# MBO.net
KiCad netlist of a schematic drawn in EAGLE
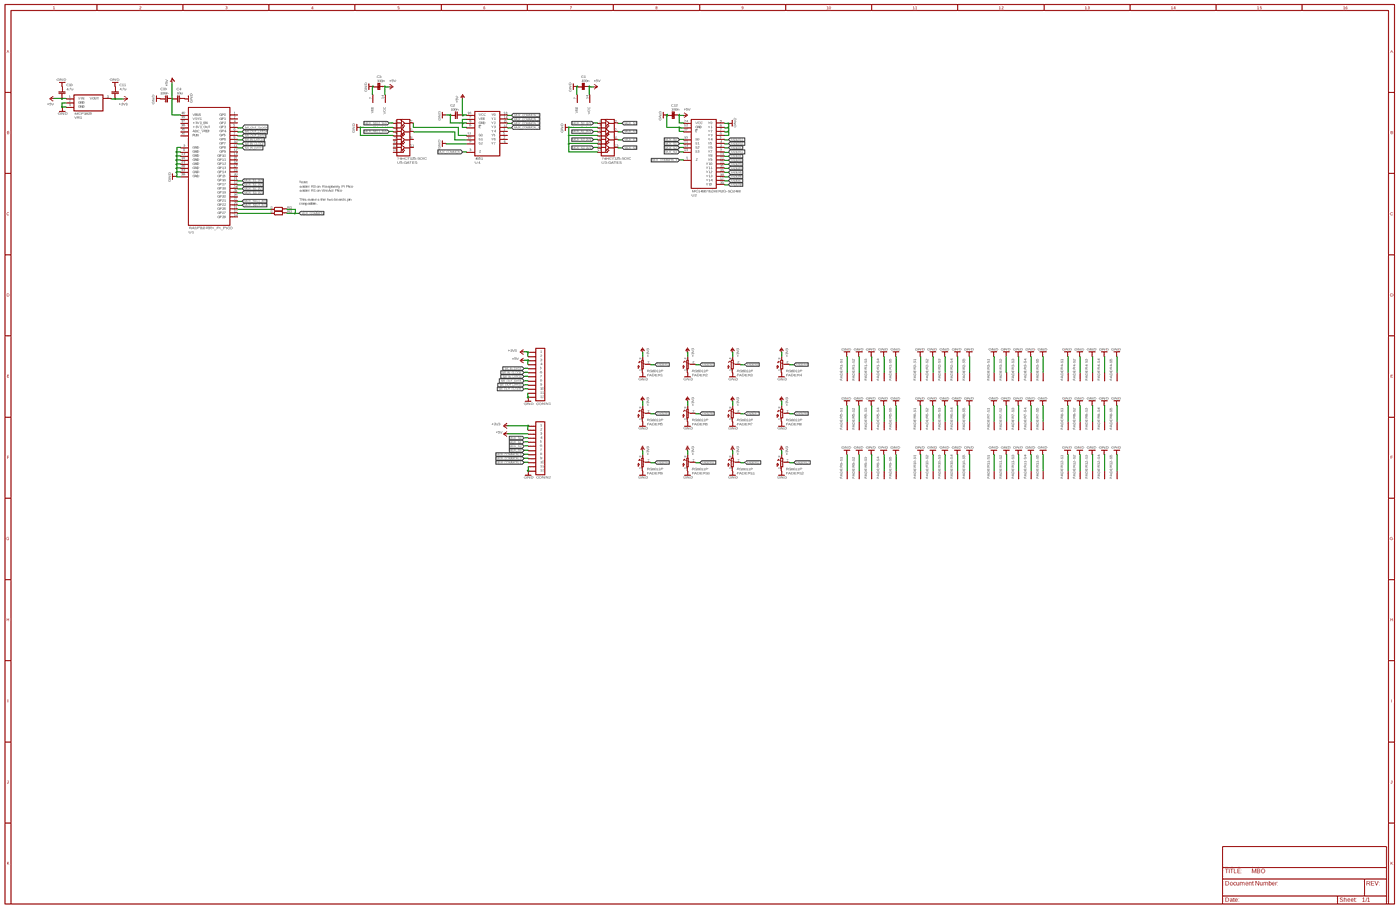
[diagram p0: schematic, sheet 1, overview]
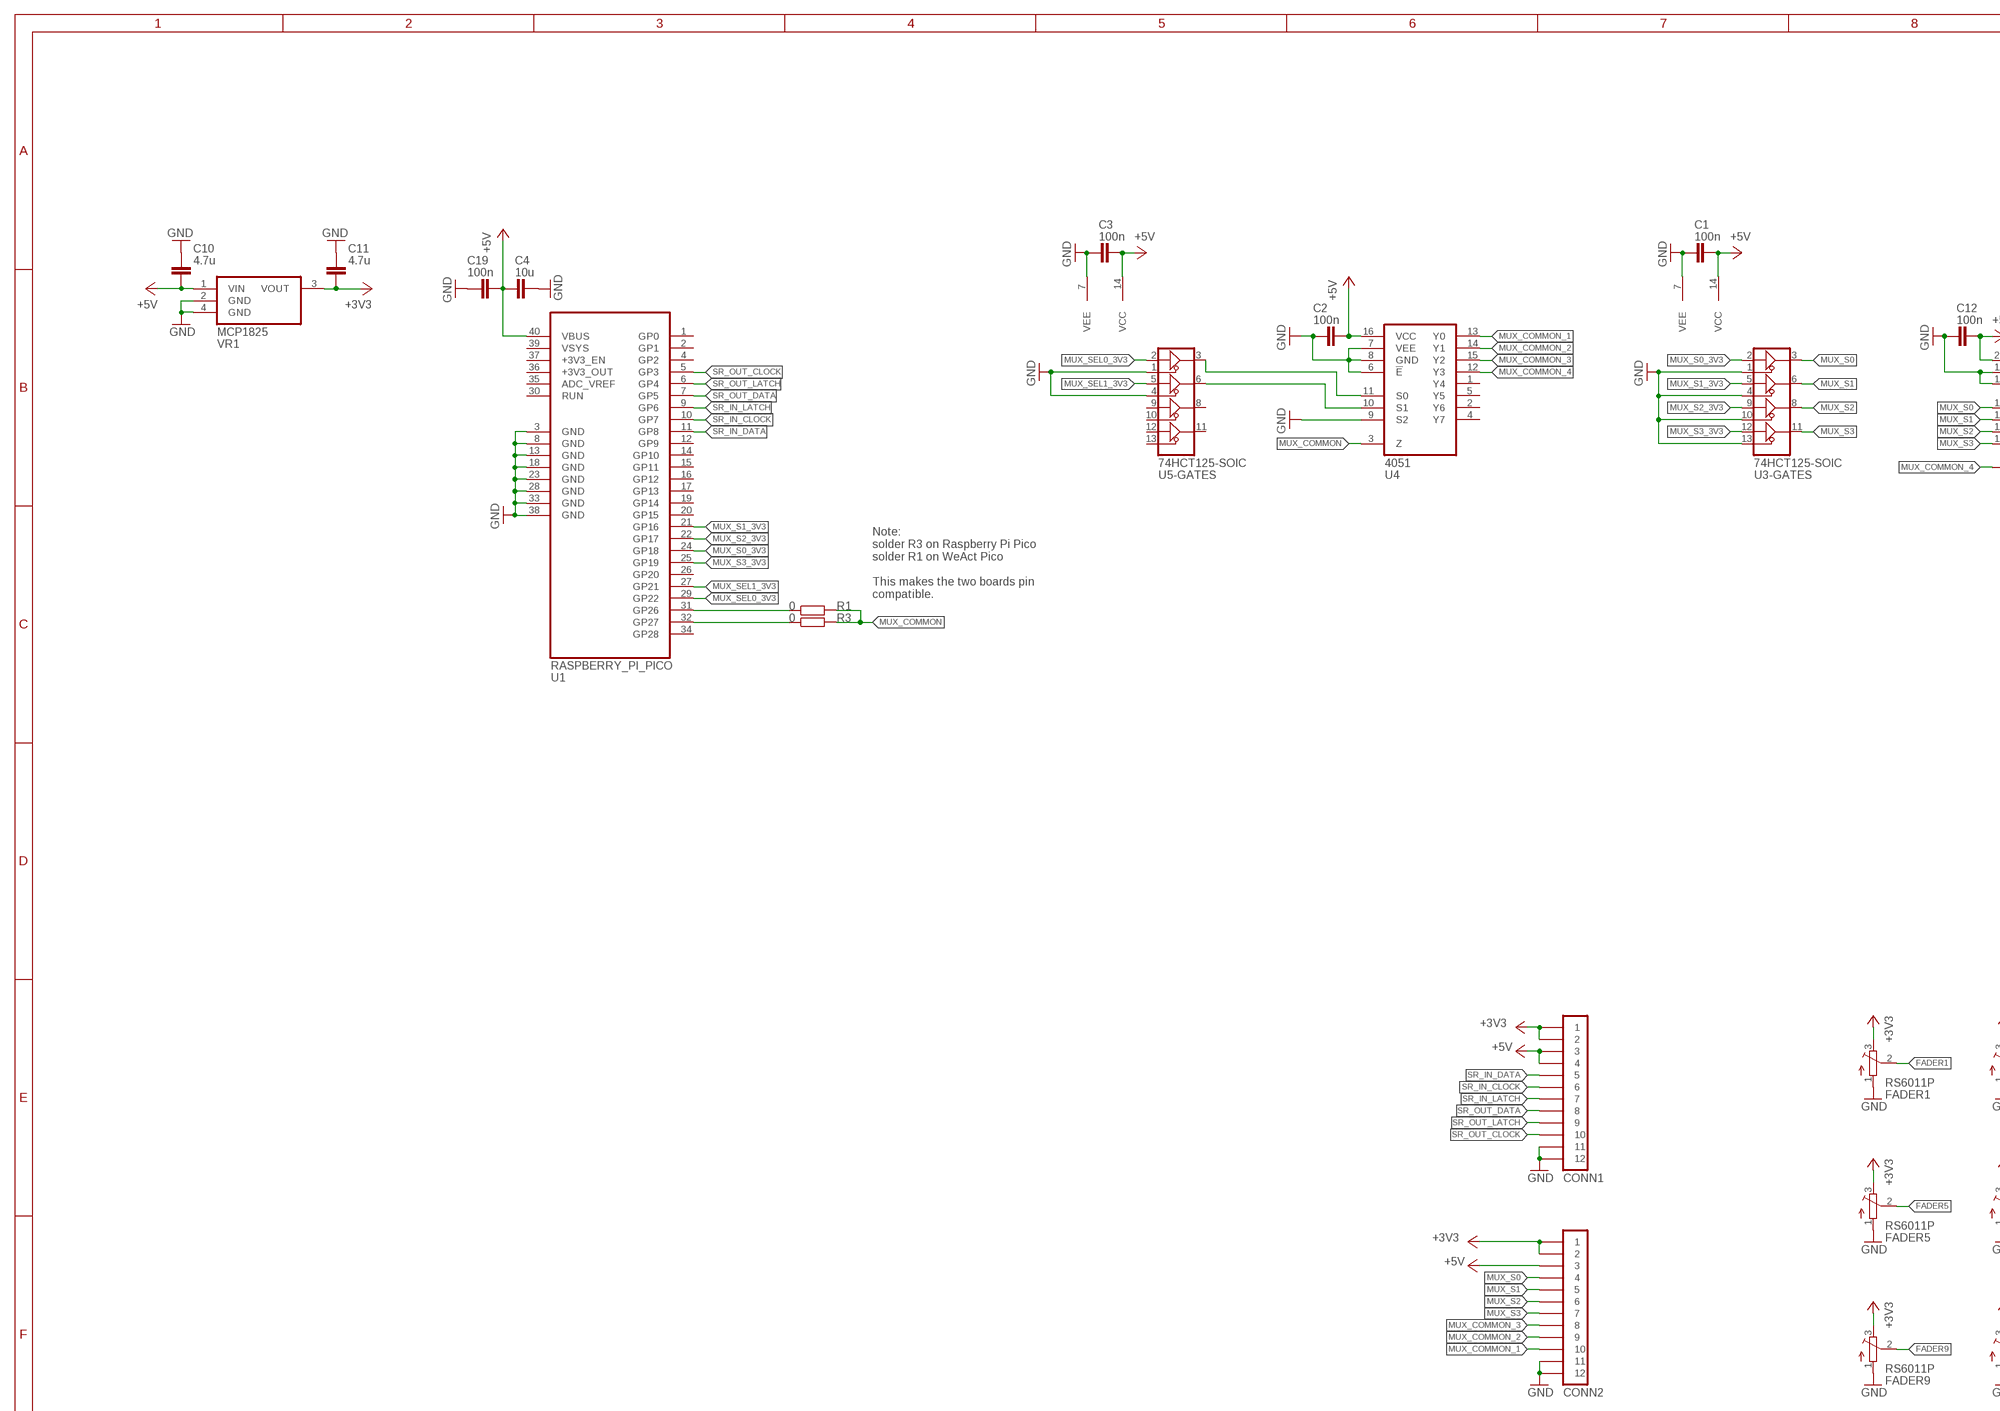
[diagram p1: schematic, sheet 1, part 1 of 4]
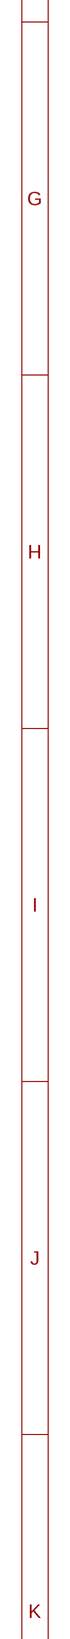
[diagram p2: schematic, sheet 1, part 2 of 4]
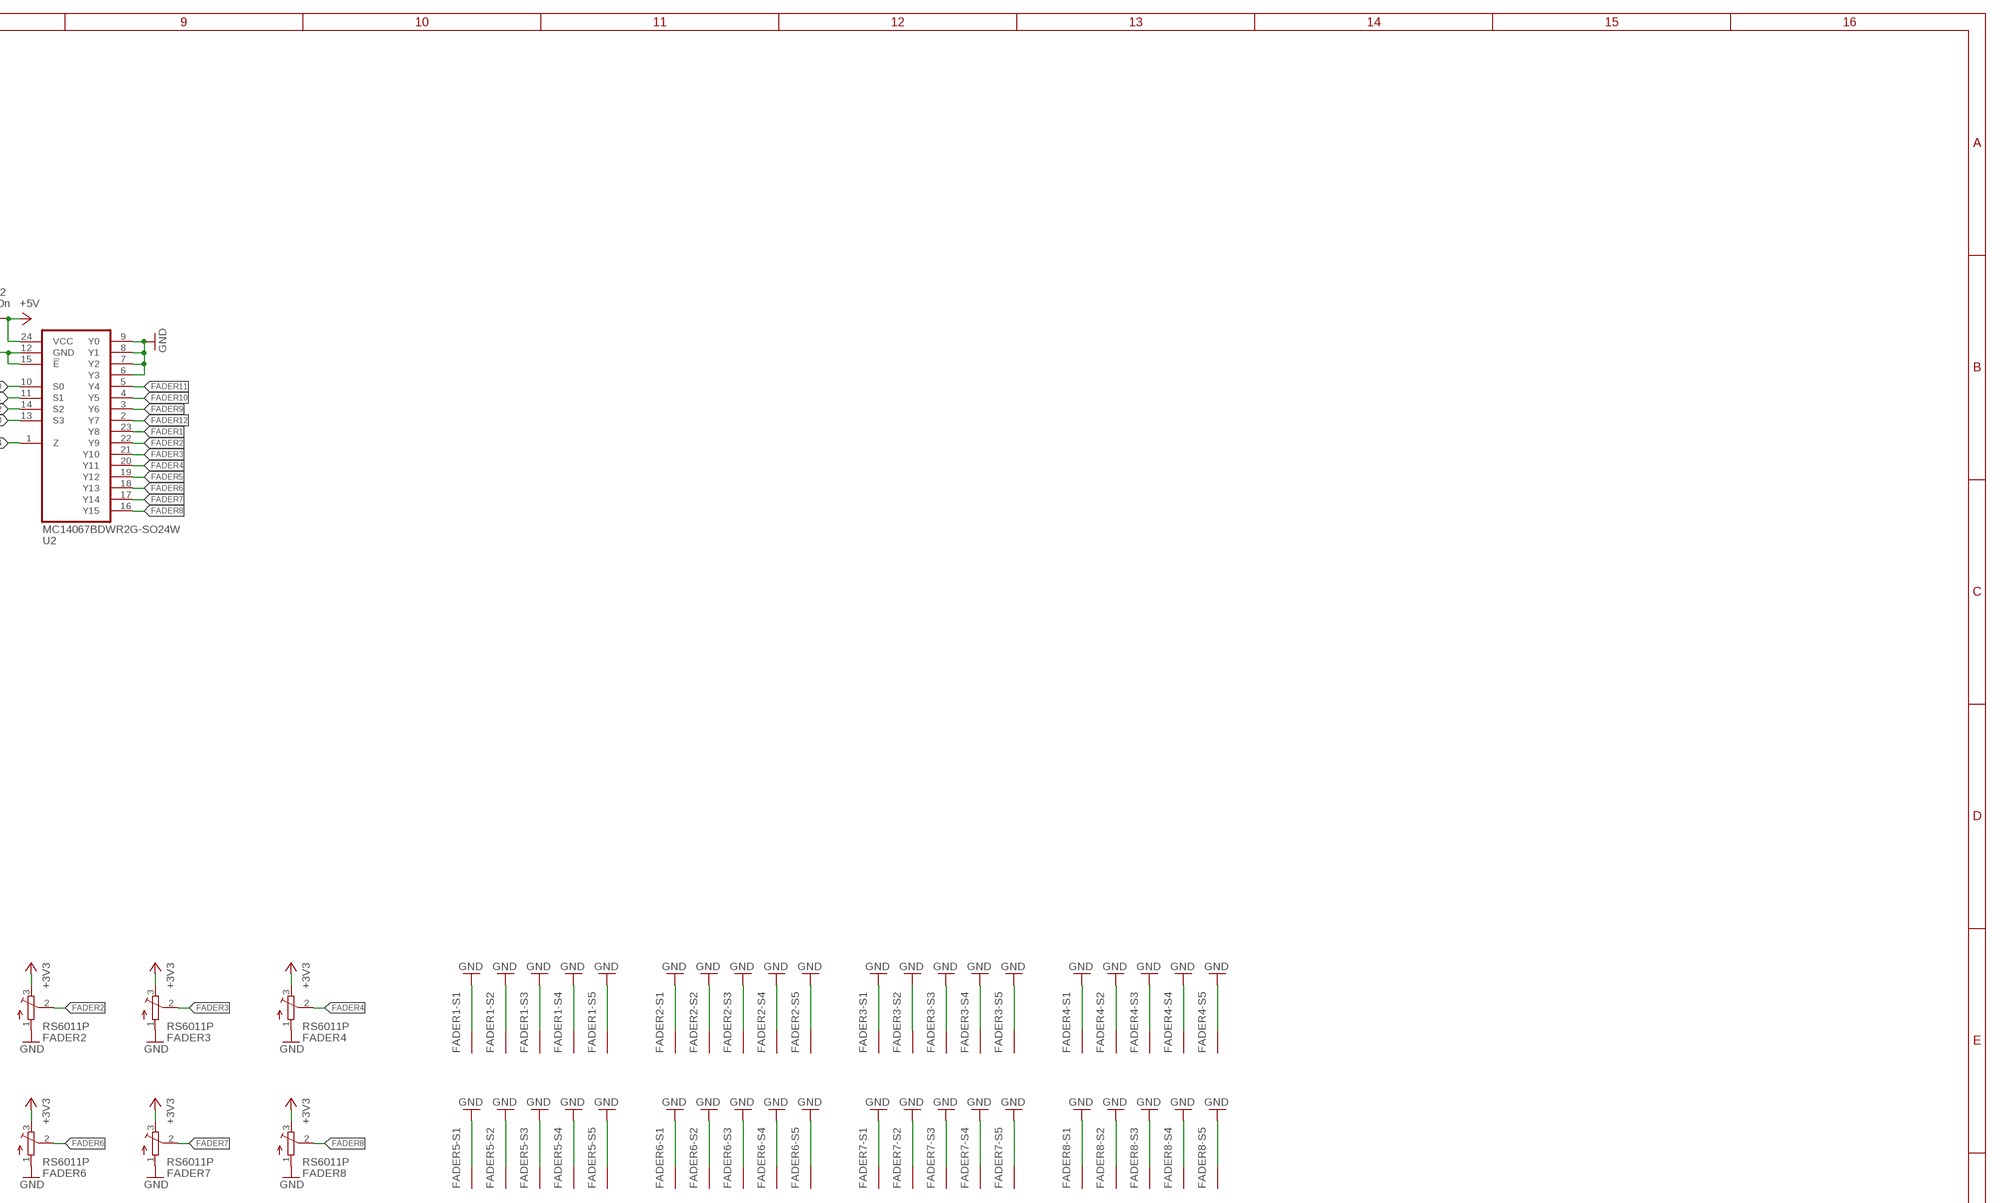
[diagram p3: schematic, sheet 1, part 3 of 4]
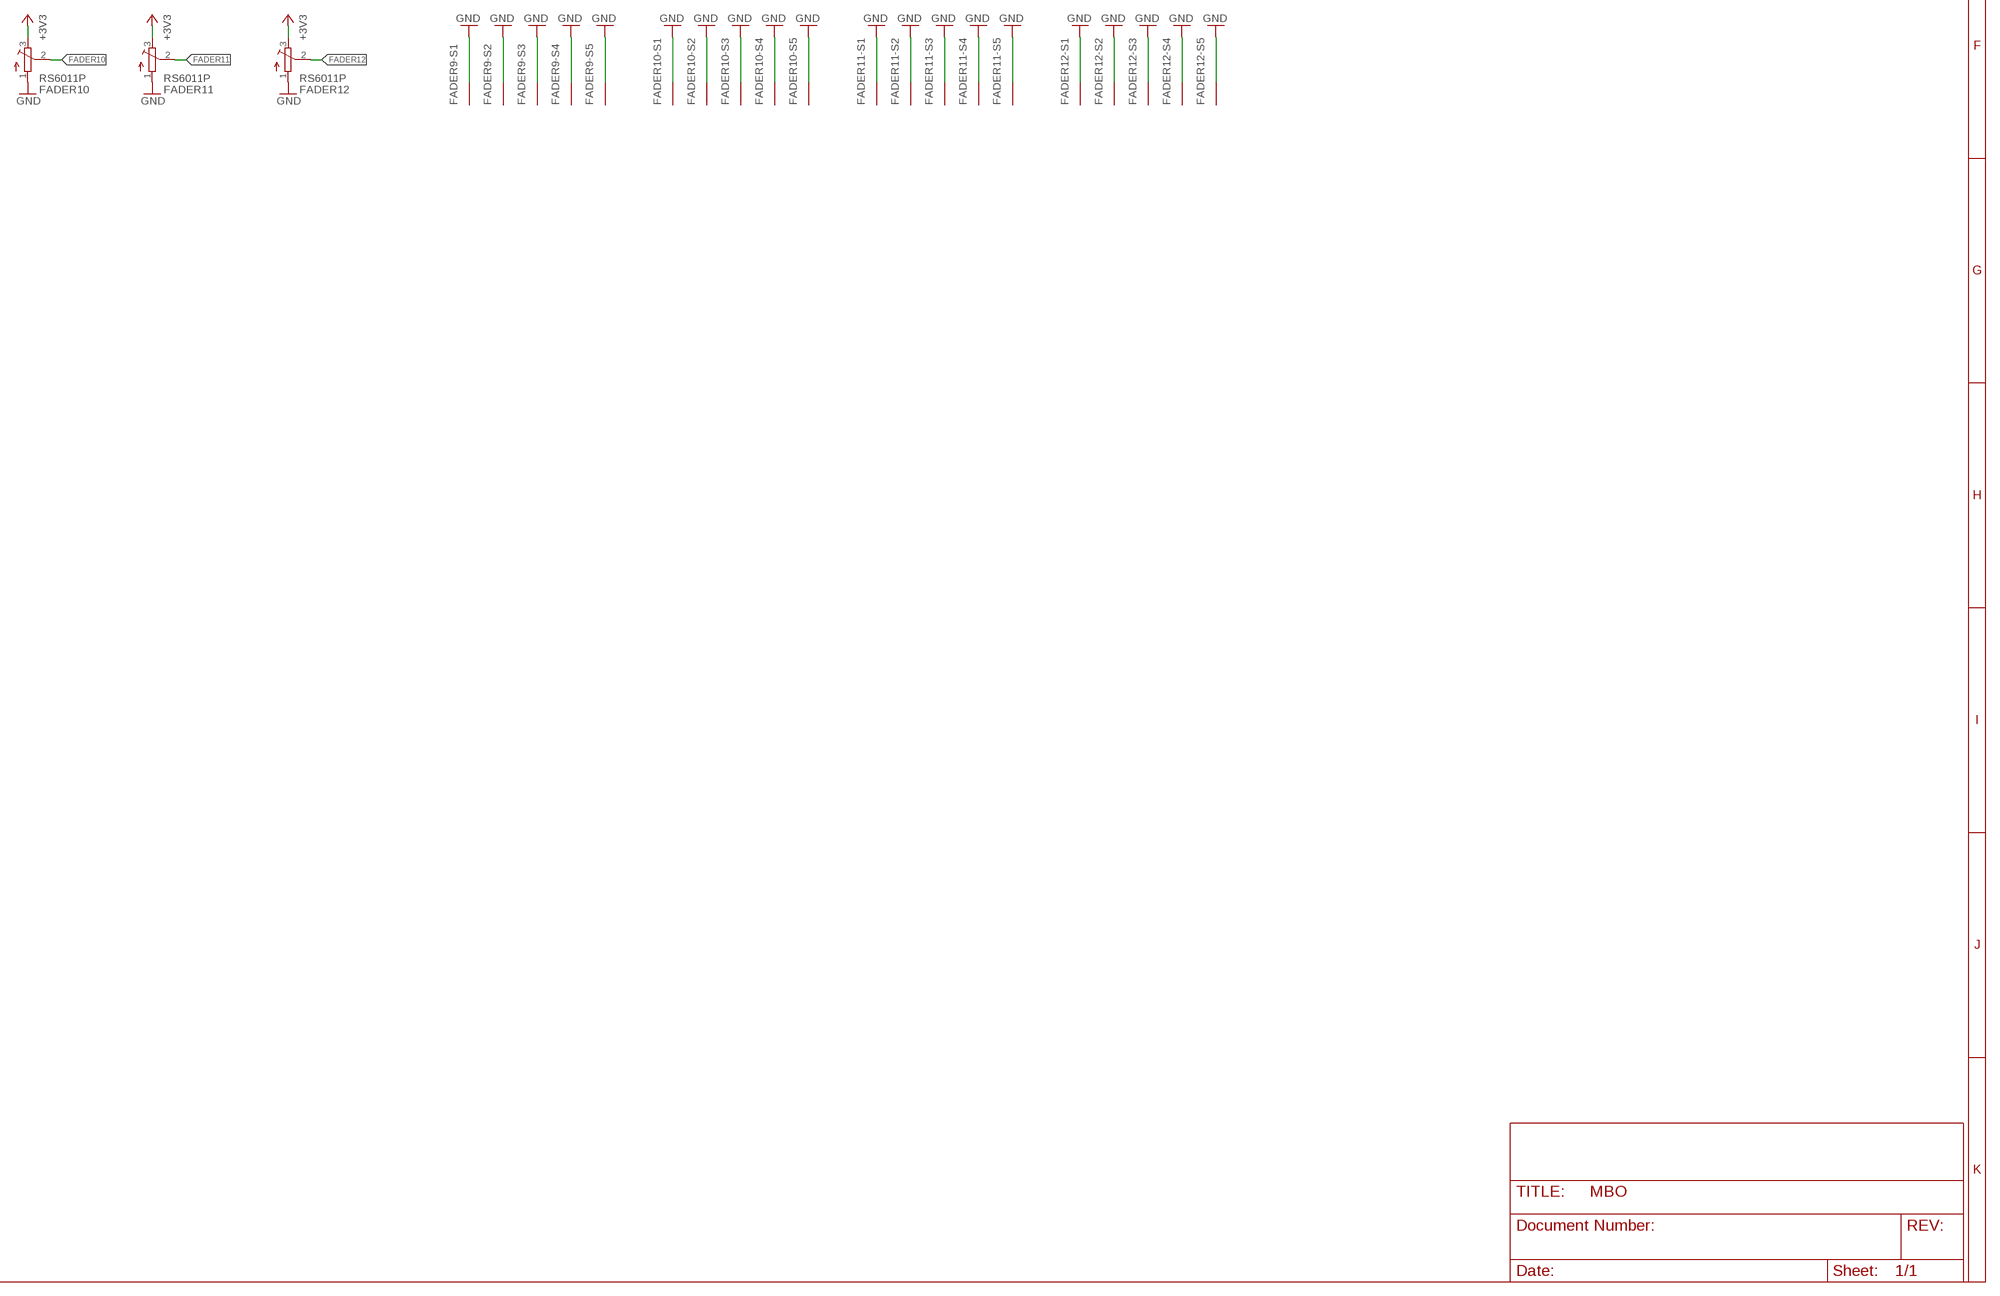
[diagram p4: schematic, sheet 1, part 4 of 4]

(export (version "E")
  (design (tool "Eeschema 10.0.6"))
  (components
    (comp (ref "C1")
      (value "100n")
      (footprint "eagle-import:C0805")
      (libsource (lib "eagle-import") (part "CAPACITOR-0805"))
    )
    (comp (ref "C2")
      (value "100n")
      (footprint "eagle-import:C0805")
      (libsource (lib "eagle-import") (part "CAPACITOR-0805"))
    )
    (comp (ref "C3")
      (value "100n")
      (footprint "eagle-import:C0805")
      (libsource (lib "eagle-import") (part "CAPACITOR-0805"))
    )
    (comp (ref "C4")
      (value "10u")
      (footprint "eagle-import:C0805")
      (libsource (lib "eagle-import") (part "CAPACITOR-0805"))
    )
    (comp (ref "C10")
      (value "4.7u")
      (footprint "eagle-import:C0805")
      (libsource (lib "eagle-import") (part "CAPACITOR-0805"))
    )
    (comp (ref "C11")
      (value "4.7u")
      (footprint "eagle-import:C0805")
      (libsource (lib "eagle-import") (part "CAPACITOR-0805"))
    )
    (comp (ref "C12")
      (value "100n")
      (footprint "eagle-import:C0805")
      (libsource (lib "eagle-import") (part "CAPACITOR-0805"))
    )
    (comp (ref "C19")
      (value "100n")
      (footprint "eagle-import:C0805")
      (libsource (lib "eagle-import") (part "CAPACITOR-0805"))
    )
    (comp (ref "CONN1")
      (value "PINHD-1X12-SMD")
      (footprint "eagle-import:MOLEX-52271-1279")
      (fields (field (name "MANUFACTURER") "Molex") (field (name "MPN") "52271-1279"))
      (libsource (lib "eagle-import") (part "PINHD-1X12-SMD"))
    )
    (comp (ref "CONN2")
      (value "PINHD-1X12-SMD")
      (footprint "eagle-import:MOLEX-52271-1279")
      (fields (field (name "MANUFACTURER") "Molex") (field (name "MPN") "52271-1279"))
      (libsource (lib "eagle-import") (part "PINHD-1X12-SMD"))
    )
    (comp (ref "FADER1")
      (value "RS6011P")
      (footprint "eagle-import:RS6011_P")
      (libsource (lib "eagle-import") (part "RS6011P"))
    )
    (comp (ref "FADER2")
      (value "RS6011P")
      (footprint "eagle-import:RS6011_P")
      (libsource (lib "eagle-import") (part "RS6011P"))
    )
    (comp (ref "FADER3")
      (value "RS6011P")
      (footprint "eagle-import:RS6011_P")
      (libsource (lib "eagle-import") (part "RS6011P"))
    )
    (comp (ref "FADER4")
      (value "RS6011P")
      (footprint "eagle-import:RS6011_P")
      (libsource (lib "eagle-import") (part "RS6011P"))
    )
    (comp (ref "FADER5")
      (value "RS6011P")
      (footprint "eagle-import:RS6011_P")
      (libsource (lib "eagle-import") (part "RS6011P"))
    )
    (comp (ref "FADER6")
      (value "RS6011P")
      (footprint "eagle-import:RS6011_P")
      (libsource (lib "eagle-import") (part "RS6011P"))
    )
    (comp (ref "FADER7")
      (value "RS6011P")
      (footprint "eagle-import:RS6011_P")
      (libsource (lib "eagle-import") (part "RS6011P"))
    )
    (comp (ref "FADER8")
      (value "RS6011P")
      (footprint "eagle-import:RS6011_P")
      (libsource (lib "eagle-import") (part "RS6011P"))
    )
    (comp (ref "FADER9")
      (value "RS6011P")
      (footprint "eagle-import:RS6011_P")
      (libsource (lib "eagle-import") (part "RS6011P"))
    )
    (comp (ref "FADER10")
      (value "RS6011P")
      (footprint "eagle-import:RS6011_P")
      (libsource (lib "eagle-import") (part "RS6011P"))
    )
    (comp (ref "FADER11")
      (value "RS6011P")
      (footprint "eagle-import:RS6011_P")
      (libsource (lib "eagle-import") (part "RS6011P"))
    )
    (comp (ref "FADER12")
      (value "RS6011P")
      (footprint "eagle-import:RS6011_P")
      (libsource (lib "eagle-import") (part "RS6011P"))
    )
    (comp (ref "R1")
      (value "0")
      (footprint "eagle-import:R0805")
      (libsource (lib "eagle-import") (part "RESISTOR-0805"))
    )
    (comp (ref "R3")
      (value "0")
      (footprint "eagle-import:R0805")
      (libsource (lib "eagle-import") (part "RESISTOR-0805"))
    )
    (comp (ref "U1")
      (value "RASPBERRY_PI_PICO")
      (footprint "eagle-import:RASPBERRY_PI_PICO")
      (libsource (lib "eagle-import") (part "RASPBERRY_PI_PICO"))
    )
    (comp (ref "U2")
      (value "MC14067BDWR2G-SO24W")
      (footprint "eagle-import:SO24-W")
      (fields (field (name "MANUFACTURER") "ON Semiconductor") (field (name "MPN") "MC14067BDWR2G"))
      (libsource (lib "eagle-import") (part "MC14067BDWR2G-SO24W"))
    )
    (comp (ref "U3")
      (value "74HCT125-SOIC")
      (footprint "eagle-import:SOIC14")
      (fields (field (name "MANUFACTURER") "Nexperia") (field (name "MPN") "74HCT125D"))
      (libsource (lib "eagle-import") (part "74125-SOICHCT"))
    )
    (comp (ref "U4")
      (value "4051")
      (footprint "eagle-import:SO16")
      (libsource (lib "eagle-import") (part "4051"))
    )
    (comp (ref "U5")
      (value "74HCT125-SOIC")
      (footprint "eagle-import:SOIC14")
      (fields (field (name "MANUFACTURER") "Nexperia") (field (name "MPN") "74HCT125D"))
      (libsource (lib "eagle-import") (part "74125-SOICHCT"))
    )
    (comp (ref "VR1")
      (value "MCP1825")
      (footprint "eagle-import:SOT223")
      (fields (field (name "MANUFACTURER") "Microchip") (field (name "MPN") "MCP1825S-3302E/DB"))
      (libsource (lib "eagle-import") (part "MCP1825"))
    )
  )
  (nets
    (net (code "1") (name "+3V3") (class "Default")
      (node (ref "C11") (pin "1") (pinfunction "1_1") (pintype "passive"))
      (node (ref "CONN1") (pin "1") (pinfunction "1_1") (pintype "passive"))
      (node (ref "CONN1") (pin "2") (pinfunction "2_2") (pintype "passive"))
      (node (ref "CONN2") (pin "1") (pinfunction "1_1") (pintype "passive"))
      (node (ref "CONN2") (pin "2") (pinfunction "2_2") (pintype "passive"))
      (node (ref "FADER1") (pin "3") (pinfunction "3_3") (pintype "passive"))
      (node (ref "FADER10") (pin "3") (pinfunction "3_3") (pintype "passive"))
      (node (ref "FADER11") (pin "3") (pinfunction "3_3") (pintype "passive"))
      (node (ref "FADER12") (pin "3") (pinfunction "3_3") (pintype "passive"))
      (node (ref "FADER2") (pin "3") (pinfunction "3_3") (pintype "passive"))
      (node (ref "FADER3") (pin "3") (pinfunction "3_3") (pintype "passive"))
      (node (ref "FADER4") (pin "3") (pinfunction "3_3") (pintype "passive"))
      (node (ref "FADER5") (pin "3") (pinfunction "3_3") (pintype "passive"))
      (node (ref "FADER6") (pin "3") (pinfunction "3_3") (pintype "passive"))
      (node (ref "FADER7") (pin "3") (pinfunction "3_3") (pintype "passive"))
      (node (ref "FADER8") (pin "3") (pinfunction "3_3") (pintype "passive"))
      (node (ref "FADER9") (pin "3") (pinfunction "3_3") (pintype "passive"))
      (node (ref "VR1") (pin "3") (pinfunction "VOUT_3") (pintype "passive"))
    )
    (net (code "2") (name "+5V") (class "Default")
      (node (ref "C1") (pin "1") (pinfunction "1_1") (pintype "passive"))
      (node (ref "C10") (pin "1") (pinfunction "1_1") (pintype "passive"))
      (node (ref "C12") (pin "1") (pinfunction "1_1") (pintype "passive"))
      (node (ref "C19") (pin "1") (pinfunction "1_1") (pintype "passive"))
      (node (ref "C2") (pin "1") (pinfunction "1_1") (pintype "passive"))
      (node (ref "C3") (pin "1") (pinfunction "1_1") (pintype "passive"))
      (node (ref "C4") (pin "2") (pinfunction "2_2") (pintype "passive"))
      (node (ref "CONN1") (pin "3") (pinfunction "3_3") (pintype "passive"))
      (node (ref "CONN1") (pin "4") (pinfunction "4_4") (pintype "passive"))
      (node (ref "CONN2") (pin "3") (pinfunction "3_3") (pintype "passive"))
      (node (ref "U1") (pin "40") (pinfunction "VBUS_40") (pintype "bidirectional"))
      (node (ref "U2") (pin "24") (pinfunction "VCC_24") (pintype "passive"))
      (node (ref "U3") (pin "14") (pinfunction "VCC_14") (pintype "passive"))
      (node (ref "U4") (pin "16") (pinfunction "VCC_16") (pintype "passive"))
      (node (ref "U5") (pin "14") (pinfunction "VCC_14") (pintype "passive"))
      (node (ref "VR1") (pin "1") (pinfunction "VIN_1") (pintype "passive"))
    )
    (net (code "3") (name "FADER1") (class "Default")
      (node (ref "FADER1") (pin "2") (pinfunction "2_2") (pintype "passive"))
      (node (ref "U2") (pin "23") (pinfunction "Y8_23") (pintype "bidirectional"))
    )
    (net (code "4") (name "FADER2") (class "Default")
      (node (ref "FADER2") (pin "2") (pinfunction "2_2") (pintype "passive"))
      (node (ref "U2") (pin "22") (pinfunction "Y9_22") (pintype "bidirectional"))
    )
    (net (code "5") (name "FADER3") (class "Default")
      (node (ref "FADER3") (pin "2") (pinfunction "2_2") (pintype "passive"))
      (node (ref "U2") (pin "21") (pinfunction "Y10_21") (pintype "bidirectional"))
    )
    (net (code "6") (name "FADER4") (class "Default")
      (node (ref "FADER4") (pin "2") (pinfunction "2_2") (pintype "passive"))
      (node (ref "U2") (pin "20") (pinfunction "Y11_20") (pintype "bidirectional"))
    )
    (net (code "7") (name "FADER5") (class "Default")
      (node (ref "FADER5") (pin "2") (pinfunction "2_2") (pintype "passive"))
      (node (ref "U2") (pin "19") (pinfunction "Y12_19") (pintype "bidirectional"))
    )
    (net (code "8") (name "FADER6") (class "Default")
      (node (ref "FADER6") (pin "2") (pinfunction "2_2") (pintype "passive"))
      (node (ref "U2") (pin "18") (pinfunction "Y13_18") (pintype "bidirectional"))
    )
    (net (code "9") (name "FADER7") (class "Default")
      (node (ref "FADER7") (pin "2") (pinfunction "2_2") (pintype "passive"))
      (node (ref "U2") (pin "17") (pinfunction "Y14_17") (pintype "bidirectional"))
    )
    (net (code "10") (name "FADER8") (class "Default")
      (node (ref "FADER8") (pin "2") (pinfunction "2_2") (pintype "passive"))
      (node (ref "U2") (pin "16") (pinfunction "Y15_16") (pintype "bidirectional"))
    )
    (net (code "11") (name "FADER9") (class "Default")
      (node (ref "FADER9") (pin "2") (pinfunction "2_2") (pintype "passive"))
      (node (ref "U2") (pin "3") (pinfunction "Y6_3") (pintype "bidirectional"))
    )
    (net (code "12") (name "FADER10") (class "Default")
      (node (ref "FADER10") (pin "2") (pinfunction "2_2") (pintype "passive"))
      (node (ref "U2") (pin "4") (pinfunction "Y5_4") (pintype "bidirectional"))
    )
    (net (code "13") (name "FADER11") (class "Default")
      (node (ref "FADER11") (pin "2") (pinfunction "2_2") (pintype "passive"))
      (node (ref "U2") (pin "5") (pinfunction "Y4_5") (pintype "bidirectional"))
    )
    (net (code "14") (name "FADER12") (class "Default")
      (node (ref "FADER12") (pin "2") (pinfunction "2_2") (pintype "passive"))
      (node (ref "U2") (pin "2") (pinfunction "Y7_2") (pintype "bidirectional"))
    )
    (net (code "15") (name "GND") (class "Default")
      (node (ref "C1") (pin "2") (pinfunction "2_2") (pintype "passive"))
      (node (ref "C10") (pin "2") (pinfunction "2_2") (pintype "passive"))
      (node (ref "C11") (pin "2") (pinfunction "2_2") (pintype "passive"))
      (node (ref "C12") (pin "2") (pinfunction "2_2") (pintype "passive"))
      (node (ref "C19") (pin "2") (pinfunction "2_2") (pintype "passive"))
      (node (ref "C2") (pin "2") (pinfunction "2_2") (pintype "passive"))
      (node (ref "C3") (pin "2") (pinfunction "2_2") (pintype "passive"))
      (node (ref "C4") (pin "1") (pinfunction "1_1") (pintype "passive"))
      (node (ref "CONN1") (pin "11") (pinfunction "11_11") (pintype "passive"))
      (node (ref "CONN1") (pin "12") (pinfunction "12_12") (pintype "passive"))
      (node (ref "CONN2") (pin "11") (pinfunction "11_11") (pintype "passive"))
      (node (ref "CONN2") (pin "12") (pinfunction "12_12") (pintype "passive"))
      (node (ref "FADER1") (pin "1") (pinfunction "1_1") (pintype "passive"))
      (node (ref "FADER1") (pin "S1") (pinfunction "S_S1") (pintype "passive"))
      (node (ref "FADER1") (pin "S2") (pinfunction "S_S2") (pintype "passive"))
      (node (ref "FADER1") (pin "S3") (pinfunction "S_S3") (pintype "passive"))
      (node (ref "FADER1") (pin "S4") (pinfunction "S_S4") (pintype "passive"))
      (node (ref "FADER1") (pin "S5") (pinfunction "S_S5") (pintype "passive"))
      (node (ref "FADER10") (pin "1") (pinfunction "1_1") (pintype "passive"))
      (node (ref "FADER10") (pin "S1") (pinfunction "S_S1") (pintype "passive"))
      (node (ref "FADER10") (pin "S2") (pinfunction "S_S2") (pintype "passive"))
      (node (ref "FADER10") (pin "S3") (pinfunction "S_S3") (pintype "passive"))
      (node (ref "FADER10") (pin "S4") (pinfunction "S_S4") (pintype "passive"))
      (node (ref "FADER10") (pin "S5") (pinfunction "S_S5") (pintype "passive"))
      (node (ref "FADER11") (pin "1") (pinfunction "1_1") (pintype "passive"))
      (node (ref "FADER11") (pin "S1") (pinfunction "S_S1") (pintype "passive"))
      (node (ref "FADER11") (pin "S2") (pinfunction "S_S2") (pintype "passive"))
      (node (ref "FADER11") (pin "S3") (pinfunction "S_S3") (pintype "passive"))
      (node (ref "FADER11") (pin "S4") (pinfunction "S_S4") (pintype "passive"))
      (node (ref "FADER11") (pin "S5") (pinfunction "S_S5") (pintype "passive"))
      (node (ref "FADER12") (pin "1") (pinfunction "1_1") (pintype "passive"))
      (node (ref "FADER12") (pin "S1") (pinfunction "S_S1") (pintype "passive"))
      (node (ref "FADER12") (pin "S2") (pinfunction "S_S2") (pintype "passive"))
      (node (ref "FADER12") (pin "S3") (pinfunction "S_S3") (pintype "passive"))
      (node (ref "FADER12") (pin "S4") (pinfunction "S_S4") (pintype "passive"))
      (node (ref "FADER12") (pin "S5") (pinfunction "S_S5") (pintype "passive"))
      (node (ref "FADER2") (pin "1") (pinfunction "1_1") (pintype "passive"))
      (node (ref "FADER2") (pin "S1") (pinfunction "S_S1") (pintype "passive"))
      (node (ref "FADER2") (pin "S2") (pinfunction "S_S2") (pintype "passive"))
      (node (ref "FADER2") (pin "S3") (pinfunction "S_S3") (pintype "passive"))
      (node (ref "FADER2") (pin "S4") (pinfunction "S_S4") (pintype "passive"))
      (node (ref "FADER2") (pin "S5") (pinfunction "S_S5") (pintype "passive"))
      (node (ref "FADER3") (pin "1") (pinfunction "1_1") (pintype "passive"))
      (node (ref "FADER3") (pin "S1") (pinfunction "S_S1") (pintype "passive"))
      (node (ref "FADER3") (pin "S2") (pinfunction "S_S2") (pintype "passive"))
      (node (ref "FADER3") (pin "S3") (pinfunction "S_S3") (pintype "passive"))
      (node (ref "FADER3") (pin "S4") (pinfunction "S_S4") (pintype "passive"))
      (node (ref "FADER3") (pin "S5") (pinfunction "S_S5") (pintype "passive"))
      (node (ref "FADER4") (pin "1") (pinfunction "1_1") (pintype "passive"))
      (node (ref "FADER4") (pin "S1") (pinfunction "S_S1") (pintype "passive"))
      (node (ref "FADER4") (pin "S2") (pinfunction "S_S2") (pintype "passive"))
      (node (ref "FADER4") (pin "S3") (pinfunction "S_S3") (pintype "passive"))
      (node (ref "FADER4") (pin "S4") (pinfunction "S_S4") (pintype "passive"))
      (node (ref "FADER4") (pin "S5") (pinfunction "S_S5") (pintype "passive"))
      (node (ref "FADER5") (pin "1") (pinfunction "1_1") (pintype "passive"))
      (node (ref "FADER5") (pin "S1") (pinfunction "S_S1") (pintype "passive"))
      (node (ref "FADER5") (pin "S2") (pinfunction "S_S2") (pintype "passive"))
      (node (ref "FADER5") (pin "S3") (pinfunction "S_S3") (pintype "passive"))
      (node (ref "FADER5") (pin "S4") (pinfunction "S_S4") (pintype "passive"))
      (node (ref "FADER5") (pin "S5") (pinfunction "S_S5") (pintype "passive"))
      (node (ref "FADER6") (pin "1") (pinfunction "1_1") (pintype "passive"))
      (node (ref "FADER6") (pin "S1") (pinfunction "S_S1") (pintype "passive"))
      (node (ref "FADER6") (pin "S2") (pinfunction "S_S2") (pintype "passive"))
      (node (ref "FADER6") (pin "S3") (pinfunction "S_S3") (pintype "passive"))
      (node (ref "FADER6") (pin "S4") (pinfunction "S_S4") (pintype "passive"))
      (node (ref "FADER6") (pin "S5") (pinfunction "S_S5") (pintype "passive"))
      (node (ref "FADER7") (pin "1") (pinfunction "1_1") (pintype "passive"))
      (node (ref "FADER7") (pin "S1") (pinfunction "S_S1") (pintype "passive"))
      (node (ref "FADER7") (pin "S2") (pinfunction "S_S2") (pintype "passive"))
      (node (ref "FADER7") (pin "S3") (pinfunction "S_S3") (pintype "passive"))
      (node (ref "FADER7") (pin "S4") (pinfunction "S_S4") (pintype "passive"))
      (node (ref "FADER7") (pin "S5") (pinfunction "S_S5") (pintype "passive"))
      (node (ref "FADER8") (pin "1") (pinfunction "1_1") (pintype "passive"))
      (node (ref "FADER8") (pin "S1") (pinfunction "S_S1") (pintype "passive"))
      (node (ref "FADER8") (pin "S2") (pinfunction "S_S2") (pintype "passive"))
      (node (ref "FADER8") (pin "S3") (pinfunction "S_S3") (pintype "passive"))
      (node (ref "FADER8") (pin "S4") (pinfunction "S_S4") (pintype "passive"))
      (node (ref "FADER8") (pin "S5") (pinfunction "S_S5") (pintype "passive"))
      (node (ref "FADER9") (pin "1") (pinfunction "1_1") (pintype "passive"))
      (node (ref "FADER9") (pin "S1") (pinfunction "S_S1") (pintype "passive"))
      (node (ref "FADER9") (pin "S2") (pinfunction "S_S2") (pintype "passive"))
      (node (ref "FADER9") (pin "S3") (pinfunction "S_S3") (pintype "passive"))
      (node (ref "FADER9") (pin "S4") (pinfunction "S_S4") (pintype "passive"))
      (node (ref "FADER9") (pin "S5") (pinfunction "S_S5") (pintype "passive"))
      (node (ref "U1") (pin "13") (pinfunction "GND_13") (pintype "bidirectional"))
      (node (ref "U1") (pin "18") (pinfunction "GND_18") (pintype "bidirectional"))
      (node (ref "U1") (pin "23") (pinfunction "GND_23") (pintype "bidirectional"))
      (node (ref "U1") (pin "28") (pinfunction "GND_28") (pintype "bidirectional"))
      (node (ref "U1") (pin "3") (pinfunction "GND_3") (pintype "bidirectional"))
      (node (ref "U1") (pin "33") (pinfunction "GND_33") (pintype "bidirectional"))
      (node (ref "U1") (pin "38") (pinfunction "GND_38") (pintype "bidirectional"))
      (node (ref "U1") (pin "8") (pinfunction "GND_8") (pintype "bidirectional"))
      (node (ref "U2") (pin "12") (pinfunction "GND_12") (pintype "passive"))
      (node (ref "U2") (pin "15") (pinfunction "~{E}_15") (pintype "input"))
      (node (ref "U2") (pin "6") (pinfunction "Y3_6") (pintype "bidirectional"))
      (node (ref "U2") (pin "7") (pinfunction "Y2_7") (pintype "bidirectional"))
      (node (ref "U2") (pin "8") (pinfunction "Y1_8") (pintype "bidirectional"))
      (node (ref "U2") (pin "9") (pinfunction "Y0_9") (pintype "bidirectional"))
      (node (ref "U3") (pin "1") (pinfunction "1~{(OE})_1") (pintype "bidirectional"))
      (node (ref "U3") (pin "10") (pinfunction "3~{(OE})_10") (pintype "bidirectional"))
      (node (ref "U3") (pin "13") (pinfunction "4~{(OE})_13") (pintype "bidirectional"))
      (node (ref "U3") (pin "4") (pinfunction "2~{(OE})_4") (pintype "bidirectional"))
      (node (ref "U3") (pin "7") (pinfunction "VEE_7") (pintype "passive"))
      (node (ref "U4") (pin "6") (pinfunction "~{E}_6") (pintype "input"))
      (node (ref "U4") (pin "7") (pinfunction "VEE_7") (pintype "passive"))
      (node (ref "U4") (pin "8") (pinfunction "GND_8") (pintype "passive"))
      (node (ref "U4") (pin "9") (pinfunction "S2_9") (pintype "input"))
      (node (ref "U5") (pin "1") (pinfunction "1~{(OE})_1") (pintype "bidirectional"))
      (node (ref "U5") (pin "4") (pinfunction "2~{(OE})_4") (pintype "bidirectional"))
      (node (ref "U5") (pin "7") (pinfunction "VEE_7") (pintype "passive"))
      (node (ref "VR1") (pin "2") (pinfunction "GND_2") (pintype "passive"))
      (node (ref "VR1") (pin "4") (pinfunction "GND_4") (pintype "passive"))
    )
    (net (code "16") (name "MUX_COMMON") (class "Default")
      (node (ref "R1") (pin "2") (pinfunction "2_2") (pintype "passive"))
      (node (ref "R3") (pin "2") (pinfunction "2_2") (pintype "passive"))
      (node (ref "U4") (pin "3") (pinfunction "Z_3") (pintype "bidirectional"))
    )
    (net (code "17") (name "MUX_COMMON_1") (class "Default")
      (node (ref "CONN2") (pin "10") (pinfunction "10_10") (pintype "passive"))
      (node (ref "U4") (pin "13") (pinfunction "Y0_13") (pintype "bidirectional"))
    )
    (net (code "18") (name "MUX_COMMON_2") (class "Default")
      (node (ref "CONN2") (pin "9") (pinfunction "9_9") (pintype "passive"))
      (node (ref "U4") (pin "14") (pinfunction "Y1_14") (pintype "bidirectional"))
    )
    (net (code "19") (name "MUX_COMMON_3") (class "Default")
      (node (ref "CONN2") (pin "8") (pinfunction "8_8") (pintype "passive"))
      (node (ref "U4") (pin "15") (pinfunction "Y2_15") (pintype "bidirectional"))
    )
    (net (code "20") (name "MUX_COMMON_4") (class "Default")
      (node (ref "U2") (pin "1") (pinfunction "Z_1") (pintype "bidirectional"))
      (node (ref "U4") (pin "12") (pinfunction "Y3_12") (pintype "bidirectional"))
    )
    (net (code "21") (name "MUX_S0") (class "Default")
      (node (ref "CONN2") (pin "4") (pinfunction "4_4") (pintype "passive"))
      (node (ref "U2") (pin "10") (pinfunction "S0_10") (pintype "input"))
      (node (ref "U3") (pin "3") (pinfunction "1Y_3") (pintype "bidirectional"))
    )
    (net (code "22") (name "MUX_S0_3V3") (class "Default")
      (node (ref "U1") (pin "24") (pinfunction "GP18_24") (pintype "bidirectional"))
      (node (ref "U3") (pin "2") (pinfunction "1A_2") (pintype "bidirectional"))
    )
    (net (code "23") (name "MUX_S1") (class "Default")
      (node (ref "CONN2") (pin "5") (pinfunction "5_5") (pintype "passive"))
      (node (ref "U2") (pin "11") (pinfunction "S1_11") (pintype "input"))
      (node (ref "U3") (pin "6") (pinfunction "2Y_6") (pintype "bidirectional"))
    )
    (net (code "24") (name "MUX_S1_3V3") (class "Default")
      (node (ref "U1") (pin "21") (pinfunction "GP16_21") (pintype "bidirectional"))
      (node (ref "U3") (pin "5") (pinfunction "2A_5") (pintype "bidirectional"))
    )
    (net (code "25") (name "MUX_S2") (class "Default")
      (node (ref "CONN2") (pin "6") (pinfunction "6_6") (pintype "passive"))
      (node (ref "U2") (pin "14") (pinfunction "S2_14") (pintype "input"))
      (node (ref "U3") (pin "8") (pinfunction "3Y_8") (pintype "bidirectional"))
    )
    (net (code "26") (name "MUX_S2_3V3") (class "Default")
      (node (ref "U1") (pin "22") (pinfunction "GP17_22") (pintype "bidirectional"))
      (node (ref "U3") (pin "9") (pinfunction "3A_9") (pintype "bidirectional"))
    )
    (net (code "27") (name "MUX_S3") (class "Default")
      (node (ref "CONN2") (pin "7") (pinfunction "7_7") (pintype "passive"))
      (node (ref "U2") (pin "13") (pinfunction "S3_13") (pintype "input"))
      (node (ref "U3") (pin "11") (pinfunction "4Y_11") (pintype "bidirectional"))
    )
    (net (code "28") (name "MUX_S3_3V3") (class "Default")
      (node (ref "U1") (pin "25") (pinfunction "GP19_25") (pintype "bidirectional"))
      (node (ref "U3") (pin "12") (pinfunction "4A_12") (pintype "bidirectional"))
    )
    (net (code "29") (name "MUX_SEL0_3V3") (class "Default")
      (node (ref "U1") (pin "29") (pinfunction "GP22_29") (pintype "bidirectional"))
      (node (ref "U5") (pin "2") (pinfunction "1A_2") (pintype "bidirectional"))
    )
    (net (code "30") (name "MUX_SEL1_3V3") (class "Default")
      (node (ref "U1") (pin "27") (pinfunction "GP21_27") (pintype "bidirectional"))
      (node (ref "U5") (pin "5") (pinfunction "2A_5") (pintype "bidirectional"))
    )
    (net (code "31") (name "Net-(U1-GP26)") (class "Default")
      (node (ref "R1") (pin "1") (pinfunction "1_1") (pintype "passive"))
      (node (ref "U1") (pin "31") (pinfunction "GP26_31") (pintype "bidirectional"))
    )
    (net (code "32") (name "Net-(U1-GP27)") (class "Default")
      (node (ref "R3") (pin "1") (pinfunction "1_1") (pintype "passive"))
      (node (ref "U1") (pin "32") (pinfunction "GP27_32") (pintype "bidirectional"))
    )
    (net (code "33") (name "Net-(U4-S0)") (class "Default")
      (node (ref "U4") (pin "11") (pinfunction "S0_11") (pintype "input"))
      (node (ref "U5") (pin "3") (pinfunction "1Y_3") (pintype "bidirectional"))
    )
    (net (code "34") (name "Net-(U4-S1)") (class "Default")
      (node (ref "U4") (pin "10") (pinfunction "S1_10") (pintype "input"))
      (node (ref "U5") (pin "6") (pinfunction "2Y_6") (pintype "bidirectional"))
    )
    (net (code "35") (name "SR_IN_CLOCK") (class "Default")
      (node (ref "CONN1") (pin "6") (pinfunction "6_6") (pintype "passive"))
      (node (ref "U1") (pin "10") (pinfunction "GP7_10") (pintype "bidirectional"))
    )
    (net (code "36") (name "SR_IN_DATA") (class "Default")
      (node (ref "CONN1") (pin "5") (pinfunction "5_5") (pintype "passive"))
      (node (ref "U1") (pin "11") (pinfunction "GP8_11") (pintype "bidirectional"))
    )
    (net (code "37") (name "SR_IN_LATCH") (class "Default")
      (node (ref "CONN1") (pin "7") (pinfunction "7_7") (pintype "passive"))
      (node (ref "U1") (pin "9") (pinfunction "GP6_9") (pintype "bidirectional"))
    )
    (net (code "38") (name "SR_OUT_CLOCK") (class "Default")
      (node (ref "CONN1") (pin "10") (pinfunction "10_10") (pintype "passive"))
      (node (ref "U1") (pin "5") (pinfunction "GP3_5") (pintype "bidirectional"))
    )
    (net (code "39") (name "SR_OUT_DATA") (class "Default")
      (node (ref "CONN1") (pin "8") (pinfunction "8_8") (pintype "passive"))
      (node (ref "U1") (pin "7") (pinfunction "GP5_7") (pintype "bidirectional"))
    )
    (net (code "40") (name "SR_OUT_LATCH") (class "Default")
      (node (ref "CONN1") (pin "9") (pinfunction "9_9") (pintype "passive"))
      (node (ref "U1") (pin "6") (pinfunction "GP4_6") (pintype "bidirectional"))
    )
    (net (code "41") (name "unconnected-(U1-+3V3_EN-Pad37)") (class "Default")
      (node (ref "U1") (pin "37") (pinfunction "+3V3_EN_37") (pintype "bidirectional"))
    )
    (net (code "42") (name "unconnected-(U1-+3V3_OUT-Pad36)") (class "Default")
      (node (ref "U1") (pin "36") (pinfunction "+3V3_OUT_36") (pintype "bidirectional"))
    )
    (net (code "43") (name "unconnected-(U1-ADC_VREF-Pad35)") (class "Default")
      (node (ref "U1") (pin "35") (pinfunction "ADC_VREF_35") (pintype "bidirectional"))
    )
    (net (code "44") (name "unconnected-(U1-GP0-Pad1)") (class "Default")
      (node (ref "U1") (pin "1") (pinfunction "GP0_1") (pintype "bidirectional"))
    )
    (net (code "45") (name "unconnected-(U1-GP1-Pad2)") (class "Default")
      (node (ref "U1") (pin "2") (pinfunction "GP1_2") (pintype "bidirectional"))
    )
    (net (code "46") (name "unconnected-(U1-GP2-Pad4)") (class "Default")
      (node (ref "U1") (pin "4") (pinfunction "GP2_4") (pintype "bidirectional"))
    )
    (net (code "47") (name "unconnected-(U1-GP9-Pad12)") (class "Default")
      (node (ref "U1") (pin "12") (pinfunction "GP9_12") (pintype "bidirectional"))
    )
    (net (code "48") (name "unconnected-(U1-GP10-Pad14)") (class "Default")
      (node (ref "U1") (pin "14") (pinfunction "GP10_14") (pintype "bidirectional"))
    )
    (net (code "49") (name "unconnected-(U1-GP11-Pad15)") (class "Default")
      (node (ref "U1") (pin "15") (pinfunction "GP11_15") (pintype "bidirectional"))
    )
    (net (code "50") (name "unconnected-(U1-GP12-Pad16)") (class "Default")
      (node (ref "U1") (pin "16") (pinfunction "GP12_16") (pintype "bidirectional"))
    )
    (net (code "51") (name "unconnected-(U1-GP13-Pad17)") (class "Default")
      (node (ref "U1") (pin "17") (pinfunction "GP13_17") (pintype "bidirectional"))
    )
    (net (code "52") (name "unconnected-(U1-GP14-Pad19)") (class "Default")
      (node (ref "U1") (pin "19") (pinfunction "GP14_19") (pintype "bidirectional"))
    )
    (net (code "53") (name "unconnected-(U1-GP15-Pad20)") (class "Default")
      (node (ref "U1") (pin "20") (pinfunction "GP15_20") (pintype "bidirectional"))
    )
    (net (code "54") (name "unconnected-(U1-GP20-Pad26)") (class "Default")
      (node (ref "U1") (pin "26") (pinfunction "GP20_26") (pintype "bidirectional"))
    )
    (net (code "55") (name "unconnected-(U1-GP28-Pad34)") (class "Default")
      (node (ref "U1") (pin "34") (pinfunction "GP28_34") (pintype "bidirectional"))
    )
    (net (code "56") (name "unconnected-(U1-RUN-Pad30)") (class "Default")
      (node (ref "U1") (pin "30") (pinfunction "RUN_30") (pintype "bidirectional"))
    )
    (net (code "57") (name "unconnected-(U1-VSYS-Pad39)") (class "Default")
      (node (ref "U1") (pin "39") (pinfunction "VSYS_39") (pintype "bidirectional"))
    )
    (net (code "58") (name "unconnected-(U4-Y4-Pad1)") (class "Default")
      (node (ref "U4") (pin "1") (pinfunction "Y4_1") (pintype "bidirectional"))
    )
    (net (code "59") (name "unconnected-(U4-Y5-Pad5)") (class "Default")
      (node (ref "U4") (pin "5") (pinfunction "Y5_5") (pintype "bidirectional"))
    )
    (net (code "60") (name "unconnected-(U4-Y6-Pad2)") (class "Default")
      (node (ref "U4") (pin "2") (pinfunction "Y6_2") (pintype "bidirectional"))
    )
    (net (code "61") (name "unconnected-(U4-Y7-Pad4)") (class "Default")
      (node (ref "U4") (pin "4") (pinfunction "Y7_4") (pintype "bidirectional"))
    )
    (net (code "62") (name "unconnected-(U5A-3A-Pad9)") (class "Default")
      (node (ref "U5") (pin "9") (pinfunction "3A_9") (pintype "bidirectional"))
    )
    (net (code "63") (name "unconnected-(U5A-3Y-Pad8)") (class "Default")
      (node (ref "U5") (pin "8") (pinfunction "3Y_8") (pintype "bidirectional"))
    )
    (net (code "64") (name "unconnected-(U5A-3~{(OE})-Pad10)") (class "Default")
      (node (ref "U5") (pin "10") (pinfunction "3~{(OE})_10") (pintype "bidirectional"))
    )
    (net (code "65") (name "unconnected-(U5A-4A-Pad12)") (class "Default")
      (node (ref "U5") (pin "12") (pinfunction "4A_12") (pintype "bidirectional"))
    )
    (net (code "66") (name "unconnected-(U5A-4Y-Pad11)") (class "Default")
      (node (ref "U5") (pin "11") (pinfunction "4Y_11") (pintype "bidirectional"))
    )
    (net (code "67") (name "unconnected-(U5A-4~{(OE})-Pad13)") (class "Default")
      (node (ref "U5") (pin "13") (pinfunction "4~{(OE})_13") (pintype "bidirectional"))
    )
  )
)
